# Processor.net
KiCad netlist of a schematic drawn in Altium Designer
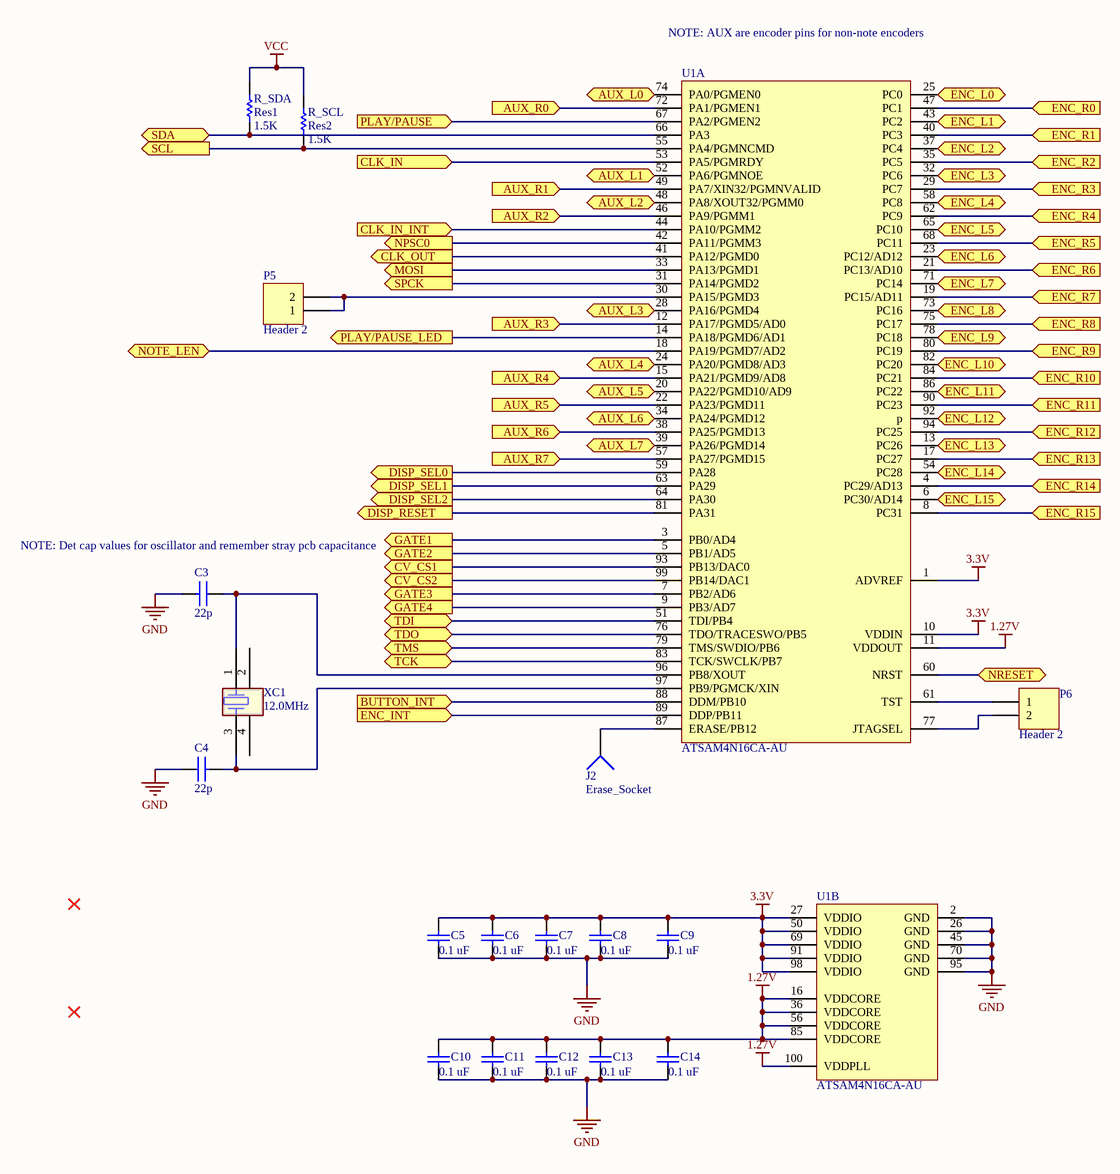
[diagram p0: Processor.SchDoc]

(export (version "E")
  (design (tool "Eeschema 10.0.6"))
  (components
    (comp (ref "C3")
      (value "22p")
      (footprint "AP1-00001")
      (description "Ceramic capacitor, SMD 0402, NP0, 50V, +/-5%")
      (fields (field (name "TOLERANCE") "50V, +/-5%") (field (name "Comment") "CAP-NONPOL"))
      (libsource (lib "AltiumDbLib") (part "CAP-NONPOL"))
    )
    (comp (ref "C4")
      (value "22p")
      (footprint "AP1-00001")
      (description "Ceramic capacitor, SMD 0402, NP0, 50V, +/-5%")
      (fields (field (name "TOLERANCE") "50V, +/-5%") (field (name "Comment") "CAP-NONPOL"))
      (libsource (lib "AltiumDbLib") (part "CAP-NONPOL"))
    )
    (comp (ref "C5")
      (value "0.1 uF")
      (footprint "C0805")
      (description "Capacitor")
      (fields (field (name "PUBLISHER") "Altium Limited"))
      (libsource (lib "Miscellaneous Devices") (part "Cap"))
    )
    (comp (ref "C6")
      (value "0.1 uF")
      (footprint "C0805")
      (description "Capacitor")
      (fields (field (name "PUBLISHER") "Altium Limited"))
      (libsource (lib "Miscellaneous Devices") (part "Cap"))
    )
    (comp (ref "C7")
      (value "0.1 uF")
      (footprint "C0805")
      (description "Capacitor")
      (fields (field (name "PUBLISHER") "Altium Limited"))
      (libsource (lib "Miscellaneous Devices") (part "Cap"))
    )
    (comp (ref "C8")
      (value "0.1 uF")
      (footprint "C0805")
      (description "Capacitor")
      (fields (field (name "PUBLISHER") "Altium Limited"))
      (libsource (lib "Miscellaneous Devices") (part "Cap"))
    )
    (comp (ref "C9")
      (value "0.1 uF")
      (footprint "C0805")
      (description "Capacitor")
      (fields (field (name "PUBLISHER") "Altium Limited"))
      (libsource (lib "Miscellaneous Devices") (part "Cap"))
    )
    (comp (ref "C10")
      (value "0.1 uF")
      (footprint "C0805")
      (description "Capacitor")
      (fields (field (name "PUBLISHER") "Altium Limited"))
      (libsource (lib "Miscellaneous Devices") (part "Cap"))
    )
    (comp (ref "C11")
      (value "0.1 uF")
      (footprint "C0805")
      (description "Capacitor")
      (fields (field (name "PUBLISHER") "Altium Limited"))
      (libsource (lib "Miscellaneous Devices") (part "Cap"))
    )
    (comp (ref "C12")
      (value "0.1 uF")
      (footprint "C0805")
      (description "Capacitor")
      (fields (field (name "PUBLISHER") "Altium Limited"))
      (libsource (lib "Miscellaneous Devices") (part "Cap"))
    )
    (comp (ref "C13")
      (value "0.1 uF")
      (footprint "C0805")
      (description "Capacitor")
      (fields (field (name "PUBLISHER") "Altium Limited"))
      (libsource (lib "Miscellaneous Devices") (part "Cap"))
    )
    (comp (ref "C14")
      (value "0.1 uF")
      (footprint "C0805")
      (description "Capacitor")
      (fields (field (name "PUBLISHER") "Altium Limited"))
      (libsource (lib "Miscellaneous Devices") (part "Cap"))
    )
    (comp (ref "J2")
      (value "Erase_Socket")
      (footprint "PIN1")
      (description "Socket")
      (fields (field (name "PUBLISHER") "Altium Limited"))
      (libsource (lib "Miscellaneous Connectors") (part "Socket"))
    )
    (comp (ref "P5")
      (value "Header 2")
      (footprint "HDR1X2")
      (description "Header, 2-Pin")
      (fields (field (name "PUBLISHER") "Altium Limited"))
      (libsource (lib "Miscellaneous Connectors") (part "Header 2"))
    )
    (comp (ref "P6")
      (value "Header 2")
      (footprint "HDR1X2")
      (description "Header, 2-Pin")
      (fields (field (name "PUBLISHER") "Altium Limited"))
      (libsource (lib "") (part "Header 2_1"))
    )
    (comp (ref "R_SCL")
      (value "Res2")
      (footprint "AXIAL-0.3")
      (description "Resistor")
      (fields (field (name "ALTIUM_VALUE") "1.5K") (field (name "PUBLISHER") "Altium Limited"))
      (libsource (lib "Miscellaneous Devices") (part "Res1"))
    )
    (comp (ref "R_SDA")
      (value "Res1")
      (footprint "AXIAL-0.3")
      (description "Resistor")
      (fields (field (name "ALTIUM_VALUE") "1.5K") (field (name "PUBLISHER") "Altium Limited"))
      (libsource (lib "Miscellaneous Devices") (part "Res1"))
    )
    (comp (ref "U1")
      (value "ATSAM4N16CA-AU")
      (footprint "LQFP100_N")
      (libsource (lib "Atmel Microcontroller ARM") (part "ATSAM4S16CA-AU"))
    )
    (comp (ref "XC1")
      (value "12.0MHz")
      (footprint "AP7-00039")
      (description "Fox FQ5032B 12.0MHz SMD crystal 738B-12")
      (fields (field (name "TOLERANCE") "30PPM") (field (name "MANUFACTURER") "Fox  Electronics"))
      (libsource (lib "AltiumDbLib") (part "CRYSTAL1324"))
    )
  )
  (nets
    (net (code "1") (name "/AUX_L0") (class "Default")
      (node (ref "U1") (pin "74") (pinfunction "PA0/PGMEN0_74") (pintype "passive"))
    )
    (net (code "2") (name "/AUX_L1") (class "Default")
      (node (ref "U1") (pin "52") (pinfunction "PA6/PGMNOE_52") (pintype "passive"))
    )
    (net (code "3") (name "/AUX_L2") (class "Default")
      (node (ref "U1") (pin "48") (pinfunction "PA8/XOUT32/PGMM0_48") (pintype "passive"))
    )
    (net (code "4") (name "/AUX_L3") (class "Default")
      (node (ref "U1") (pin "28") (pinfunction "PA16/PGMD4_28") (pintype "passive"))
    )
    (net (code "5") (name "/AUX_L4") (class "Default")
      (node (ref "U1") (pin "24") (pinfunction "PA20/PGMD8/AD3_24") (pintype "passive"))
    )
    (net (code "6") (name "/AUX_L5") (class "Default")
      (node (ref "U1") (pin "20") (pinfunction "PA22/PGMD10/AD9_20") (pintype "passive"))
    )
    (net (code "7") (name "/AUX_L6") (class "Default")
      (node (ref "U1") (pin "34") (pinfunction "PA24/PGMD12_34") (pintype "passive"))
    )
    (net (code "8") (name "/AUX_L7") (class "Default")
      (node (ref "U1") (pin "39") (pinfunction "PA26/PGMD14_39") (pintype "passive"))
    )
    (net (code "9") (name "/AUX_R0") (class "Default")
      (node (ref "U1") (pin "72") (pinfunction "PA1/PGMEN1_72") (pintype "passive"))
    )
    (net (code "10") (name "/AUX_R1") (class "Default")
      (node (ref "U1") (pin "49") (pinfunction "PA7/XIN32/PGMNVALID_49") (pintype "passive"))
    )
    (net (code "11") (name "/AUX_R2") (class "Default")
      (node (ref "U1") (pin "46") (pinfunction "PA9/PGMM1_46") (pintype "passive"))
    )
    (net (code "12") (name "/AUX_R3") (class "Default")
      (node (ref "U1") (pin "12") (pinfunction "PA17/PGMD5/AD0_12") (pintype "passive"))
    )
    (net (code "13") (name "/AUX_R4") (class "Default")
      (node (ref "U1") (pin "15") (pinfunction "PA21/PGMD9/AD8_15") (pintype "passive"))
    )
    (net (code "14") (name "/AUX_R5") (class "Default")
      (node (ref "U1") (pin "22") (pinfunction "PA23/PGMD11_22") (pintype "passive"))
    )
    (net (code "15") (name "/AUX_R6") (class "Default")
      (node (ref "U1") (pin "38") (pinfunction "PA25/PGMD13_38") (pintype "passive"))
    )
    (net (code "16") (name "/AUX_R7") (class "Default")
      (node (ref "U1") (pin "57") (pinfunction "PA27/PGMD15_57") (pintype "passive"))
    )
    (net (code "17") (name "/BUTTON_INT") (class "Default")
      (node (ref "U1") (pin "88") (pinfunction "DDM/PB10_88") (pintype "passive"))
    )
    (net (code "18") (name "/CLK_IN") (class "Default")
      (node (ref "U1") (pin "53") (pinfunction "PA5/PGMRDY_53") (pintype "passive"))
    )
    (net (code "19") (name "/CLK_IN_INT") (class "Default")
      (node (ref "U1") (pin "44") (pinfunction "PA10/PGMM2_44") (pintype "passive"))
    )
    (net (code "20") (name "/CLK_OUT") (class "Default")
      (node (ref "U1") (pin "41") (pinfunction "PA12/PGMD0_41") (pintype "passive"))
    )
    (net (code "21") (name "/CV_CS1") (class "Default")
      (node (ref "U1") (pin "93") (pinfunction "PB13/DAC0_93") (pintype "passive"))
    )
    (net (code "22") (name "/CV_CS2") (class "Default")
      (node (ref "U1") (pin "99") (pinfunction "PB14/DAC1_99") (pintype "passive"))
    )
    (net (code "23") (name "/DISP_RESET") (class "Default")
      (node (ref "U1") (pin "81") (pinfunction "PA31_81") (pintype "passive"))
    )
    (net (code "24") (name "/DISP_SEL0") (class "Default")
      (node (ref "U1") (pin "59") (pinfunction "PA28_59") (pintype "passive"))
    )
    (net (code "25") (name "/DISP_SEL1") (class "Default")
      (node (ref "U1") (pin "63") (pinfunction "PA29_63") (pintype "passive"))
    )
    (net (code "26") (name "/DISP_SEL2") (class "Default")
      (node (ref "U1") (pin "64") (pinfunction "PA30_64") (pintype "passive"))
    )
    (net (code "27") (name "/ENC_INT") (class "Default")
      (node (ref "U1") (pin "89") (pinfunction "DDP/PB11_89") (pintype "passive"))
    )
    (net (code "28") (name "/ENC_L0") (class "Default")
      (node (ref "U1") (pin "25") (pinfunction "PC0_25") (pintype "passive"))
    )
    (net (code "29") (name "/ENC_L1") (class "Default")
      (node (ref "U1") (pin "43") (pinfunction "PC2_43") (pintype "passive"))
    )
    (net (code "30") (name "/ENC_L2") (class "Default")
      (node (ref "U1") (pin "37") (pinfunction "PC4_37") (pintype "passive"))
    )
    (net (code "31") (name "/ENC_L3") (class "Default")
      (node (ref "U1") (pin "32") (pinfunction "PC6_32") (pintype "passive"))
    )
    (net (code "32") (name "/ENC_L4") (class "Default")
      (node (ref "U1") (pin "58") (pinfunction "PC8_58") (pintype "passive"))
    )
    (net (code "33") (name "/ENC_L5") (class "Default")
      (node (ref "U1") (pin "65") (pinfunction "PC10_65") (pintype "passive"))
    )
    (net (code "34") (name "/ENC_L6") (class "Default")
      (node (ref "U1") (pin "23") (pinfunction "PC12/AD12_23") (pintype "passive"))
    )
    (net (code "35") (name "/ENC_L7") (class "Default")
      (node (ref "U1") (pin "71") (pinfunction "PC14_71") (pintype "passive"))
    )
    (net (code "36") (name "/ENC_L8") (class "Default")
      (node (ref "U1") (pin "73") (pinfunction "PC16_73") (pintype "passive"))
    )
    (net (code "37") (name "/ENC_L9") (class "Default")
      (node (ref "U1") (pin "78") (pinfunction "PC18_78") (pintype "passive"))
    )
    (net (code "38") (name "/ENC_L10") (class "Default")
      (node (ref "U1") (pin "82") (pinfunction "PC20_82") (pintype "passive"))
    )
    (net (code "39") (name "/ENC_L11") (class "Default")
      (node (ref "U1") (pin "86") (pinfunction "PC22_86") (pintype "passive"))
    )
    (net (code "40") (name "/ENC_L12") (class "Default")
      (node (ref "U1") (pin "92") (pinfunction "p_92") (pintype "passive"))
    )
    (net (code "41") (name "/ENC_L13") (class "Default")
      (node (ref "U1") (pin "13") (pinfunction "PC26_13") (pintype "passive"))
    )
    (net (code "42") (name "/ENC_L14") (class "Default")
      (node (ref "U1") (pin "54") (pinfunction "PC28_54") (pintype "passive"))
    )
    (net (code "43") (name "/ENC_L15") (class "Default")
      (node (ref "U1") (pin "6") (pinfunction "PC30/AD14_6") (pintype "passive"))
    )
    (net (code "44") (name "/ENC_R0") (class "Default")
      (node (ref "U1") (pin "47") (pinfunction "PC1_47") (pintype "passive"))
    )
    (net (code "45") (name "/ENC_R1") (class "Default")
      (node (ref "U1") (pin "40") (pinfunction "PC3_40") (pintype "passive"))
    )
    (net (code "46") (name "/ENC_R2") (class "Default")
      (node (ref "U1") (pin "35") (pinfunction "PC5_35") (pintype "passive"))
    )
    (net (code "47") (name "/ENC_R3") (class "Default")
      (node (ref "U1") (pin "29") (pinfunction "PC7_29") (pintype "passive"))
    )
    (net (code "48") (name "/ENC_R4") (class "Default")
      (node (ref "U1") (pin "62") (pinfunction "PC9_62") (pintype "passive"))
    )
    (net (code "49") (name "/ENC_R5") (class "Default")
      (node (ref "U1") (pin "68") (pinfunction "PC11_68") (pintype "passive"))
    )
    (net (code "50") (name "/ENC_R6") (class "Default")
      (node (ref "U1") (pin "21") (pinfunction "PC13/AD10_21") (pintype "passive"))
    )
    (net (code "51") (name "/ENC_R7") (class "Default")
      (node (ref "U1") (pin "19") (pinfunction "PC15/AD11_19") (pintype "passive"))
    )
    (net (code "52") (name "/ENC_R8") (class "Default")
      (node (ref "U1") (pin "75") (pinfunction "PC17_75") (pintype "passive"))
    )
    (net (code "53") (name "/ENC_R9") (class "Default")
      (node (ref "U1") (pin "80") (pinfunction "PC19_80") (pintype "passive"))
    )
    (net (code "54") (name "/ENC_R10") (class "Default")
      (node (ref "U1") (pin "84") (pinfunction "PC21_84") (pintype "passive"))
    )
    (net (code "55") (name "/ENC_R11") (class "Default")
      (node (ref "U1") (pin "90") (pinfunction "PC23_90") (pintype "passive"))
    )
    (net (code "56") (name "/ENC_R12") (class "Default")
      (node (ref "U1") (pin "94") (pinfunction "PC25_94") (pintype "passive"))
    )
    (net (code "57") (name "/ENC_R13") (class "Default")
      (node (ref "U1") (pin "17") (pinfunction "PC27_17") (pintype "passive"))
    )
    (net (code "58") (name "/ENC_R14") (class "Default")
      (node (ref "U1") (pin "4") (pinfunction "PC29/AD13_4") (pintype "passive"))
    )
    (net (code "59") (name "/ENC_R15") (class "Default")
      (node (ref "U1") (pin "8") (pinfunction "PC31_8") (pintype "passive"))
    )
    (net (code "60") (name "/GATE1") (class "Default")
      (node (ref "U1") (pin "3") (pinfunction "PB0/AD4_3") (pintype "passive"))
    )
    (net (code "61") (name "/GATE2") (class "Default")
      (node (ref "U1") (pin "5") (pinfunction "PB1/AD5_5") (pintype "passive"))
    )
    (net (code "62") (name "/GATE3") (class "Default")
      (node (ref "U1") (pin "7") (pinfunction "PB2/AD6_7") (pintype "passive"))
    )
    (net (code "63") (name "/GATE4") (class "Default")
      (node (ref "U1") (pin "9") (pinfunction "PB3/AD7_9") (pintype "passive"))
    )
    (net (code "64") (name "/MOSI") (class "Default")
      (node (ref "U1") (pin "33") (pinfunction "PA13/PGMD1_33") (pintype "passive"))
    )
    (net (code "65") (name "/NOTE_LEN") (class "Default")
      (node (ref "U1") (pin "18") (pinfunction "PA19/PGMD7/AD2_18") (pintype "passive"))
    )
    (net (code "66") (name "/NPSC0") (class "Default")
      (node (ref "U1") (pin "42") (pinfunction "PA11/PGMM3_42") (pintype "passive"))
    )
    (net (code "67") (name "/NRESET") (class "Default")
      (node (ref "U1") (pin "60") (pinfunction "NRST_60") (pintype "passive"))
    )
    (net (code "68") (name "/PLAY{slash}PAUSE") (class "Default")
      (node (ref "U1") (pin "67") (pinfunction "PA2/PGMEN2_67") (pintype "passive"))
    )
    (net (code "69") (name "/PLAY{slash}PAUSE_LED") (class "Default")
      (node (ref "U1") (pin "14") (pinfunction "PA18/PGMD6/AD1_14") (pintype "passive"))
    )
    (net (code "70") (name "/SCL") (class "Default")
      (node (ref "R_SCL") (pin "1") (pinfunction "1_1") (pintype "passive"))
      (node (ref "U1") (pin "55") (pinfunction "PA4/PGMNCMD_55") (pintype "passive"))
    )
    (net (code "71") (name "/SDA") (class "Default")
      (node (ref "R_SDA") (pin "1") (pinfunction "1_1") (pintype "passive"))
      (node (ref "U1") (pin "66") (pinfunction "PA3_66") (pintype "passive"))
    )
    (net (code "72") (name "/SPCK") (class "Default")
      (node (ref "U1") (pin "31") (pinfunction "PA14/PGMD2_31") (pintype "passive"))
    )
    (net (code "73") (name "/TCK") (class "Default")
      (node (ref "U1") (pin "83") (pinfunction "TCK/SWCLK/PB7_83") (pintype "passive"))
    )
    (net (code "74") (name "/TDI") (class "Default")
      (node (ref "U1") (pin "51") (pinfunction "TDI/PB4_51") (pintype "passive"))
    )
    (net (code "75") (name "/TDO") (class "Default")
      (node (ref "U1") (pin "76") (pinfunction "TDO/TRACESWO/PB5_76") (pintype "passive"))
    )
    (net (code "76") (name "/TMS") (class "Default")
      (node (ref "U1") (pin "79") (pinfunction "TMS/SWDIO/PB6_79") (pintype "passive"))
    )
    (net (code "77") (name "1.27V") (class "Default")
      (node (ref "C10") (pin "2") (pinfunction "2_2") (pintype "passive"))
      (node (ref "C11") (pin "2") (pinfunction "2_2") (pintype "passive"))
      (node (ref "C12") (pin "2") (pinfunction "2_2") (pintype "passive"))
      (node (ref "C13") (pin "2") (pinfunction "2_2") (pintype "passive"))
      (node (ref "C14") (pin "2") (pinfunction "2_2") (pintype "passive"))
      (node (ref "U1") (pin "100") (pinfunction "VDDPLL_100") (pintype "power_in"))
      (node (ref "U1") (pin "11") (pinfunction "VDDOUT_11") (pintype "power_in"))
      (node (ref "U1") (pin "16") (pinfunction "VDDCORE_16") (pintype "power_in"))
      (node (ref "U1") (pin "36") (pinfunction "VDDCORE_36") (pintype "power_in"))
      (node (ref "U1") (pin "56") (pinfunction "VDDCORE_56") (pintype "power_in"))
      (node (ref "U1") (pin "85") (pinfunction "VDDCORE_85") (pintype "power_in"))
    )
    (net (code "78") (name "3.3V") (class "Default")
      (node (ref "C5") (pin "2") (pinfunction "2_2") (pintype "passive"))
      (node (ref "C6") (pin "2") (pinfunction "2_2") (pintype "passive"))
      (node (ref "C7") (pin "2") (pinfunction "2_2") (pintype "passive"))
      (node (ref "C8") (pin "2") (pinfunction "2_2") (pintype "passive"))
      (node (ref "C9") (pin "2") (pinfunction "2_2") (pintype "passive"))
      (node (ref "U1") (pin "1") (pinfunction "ADVREF_1") (pintype "passive"))
      (node (ref "U1") (pin "10") (pinfunction "VDDIN_10") (pintype "power_in"))
      (node (ref "U1") (pin "27") (pinfunction "VDDIO_27") (pintype "power_in"))
      (node (ref "U1") (pin "50") (pinfunction "VDDIO_50") (pintype "power_in"))
      (node (ref "U1") (pin "69") (pinfunction "VDDIO_69") (pintype "power_in"))
      (node (ref "U1") (pin "91") (pinfunction "VDDIO_91") (pintype "power_in"))
      (node (ref "U1") (pin "98") (pinfunction "VDDIO_98") (pintype "power_in"))
    )
    (net (code "79") (name "GND") (class "Default")
      (node (ref "C10") (pin "1") (pinfunction "1_1") (pintype "passive"))
      (node (ref "C11") (pin "1") (pinfunction "1_1") (pintype "passive"))
      (node (ref "C12") (pin "1") (pinfunction "1_1") (pintype "passive"))
      (node (ref "C13") (pin "1") (pinfunction "1_1") (pintype "passive"))
      (node (ref "C14") (pin "1") (pinfunction "1_1") (pintype "passive"))
      (node (ref "C3") (pin "2") (pinfunction "2_2") (pintype "passive"))
      (node (ref "C4") (pin "1") (pinfunction "1_1") (pintype "passive"))
      (node (ref "C5") (pin "1") (pinfunction "1_1") (pintype "passive"))
      (node (ref "C6") (pin "1") (pinfunction "1_1") (pintype "passive"))
      (node (ref "C7") (pin "1") (pinfunction "1_1") (pintype "passive"))
      (node (ref "C8") (pin "1") (pinfunction "1_1") (pintype "passive"))
      (node (ref "C9") (pin "1") (pinfunction "1_1") (pintype "passive"))
      (node (ref "U1") (pin "2") (pinfunction "GND_2") (pintype "power_in"))
      (node (ref "U1") (pin "26") (pinfunction "GND_26") (pintype "power_in"))
      (node (ref "U1") (pin "45") (pinfunction "GND_45") (pintype "power_in"))
      (node (ref "U1") (pin "70") (pinfunction "GND_70") (pintype "power_in"))
      (node (ref "U1") (pin "95") (pinfunction "GND_95") (pintype "power_in"))
    )
    (net (code "80") (name "Net-(U1A-ERASE{slash}PB12)") (class "Default")
      (node (ref "J2") (pin "1") (pinfunction "1_1") (pintype "passive"))
      (node (ref "U1") (pin "87") (pinfunction "ERASE/PB12_87") (pintype "passive"))
    )
    (net (code "81") (name "Net-(U1A-JTAGSEL)") (class "Default")
      (node (ref "P6") (pin "2") (pinfunction "2_2") (pintype "passive"))
      (node (ref "U1") (pin "77") (pinfunction "JTAGSEL_77") (pintype "passive"))
    )
    (net (code "82") (name "Net-(U1A-PA15{slash}PGMD3)") (class "Default")
      (node (ref "P5") (pin "1") (pinfunction "1_1") (pintype "passive"))
      (node (ref "P5") (pin "2") (pinfunction "2_2") (pintype "passive"))
      (node (ref "U1") (pin "30") (pinfunction "PA15/PGMD3_30") (pintype "passive"))
    )
    (net (code "83") (name "Net-(U1A-PB8{slash}XOUT)") (class "Default")
      (node (ref "C3") (pin "1") (pinfunction "1_1") (pintype "passive"))
      (node (ref "U1") (pin "96") (pinfunction "PB8/XOUT_96") (pintype "passive"))
      (node (ref "XC1") (pin "1") (pinfunction "1_1") (pintype "passive"))
    )
    (net (code "84") (name "Net-(U1A-PB9{slash}PGMCK{slash}XIN)") (class "Default")
      (node (ref "C4") (pin "2") (pinfunction "2_2") (pintype "passive"))
      (node (ref "U1") (pin "97") (pinfunction "PB9/PGMCK/XIN_97") (pintype "passive"))
      (node (ref "XC1") (pin "3") (pinfunction "3_3") (pintype "passive"))
    )
    (net (code "85") (name "Net-(U1A-TST)") (class "Default")
      (node (ref "P6") (pin "1") (pinfunction "1_1") (pintype "passive"))
      (node (ref "U1") (pin "61") (pinfunction "TST_61") (pintype "passive"))
    )
    (net (code "86") (name "VCC") (class "Default")
      (node (ref "R_SCL") (pin "2") (pinfunction "2_2") (pintype "passive"))
      (node (ref "R_SDA") (pin "2") (pinfunction "2_2") (pintype "passive"))
    )
    (net (code "87") (name "unconnected-(XC1-Pad2)") (class "Default")
      (node (ref "XC1") (pin "2") (pinfunction "2_2") (pintype "passive"))
    )
    (net (code "88") (name "unconnected-(XC1-Pad4)") (class "Default")
      (node (ref "XC1") (pin "4") (pinfunction "4_4") (pintype "passive"))
    )
  )
)
